# EasyEDA.net
KiCad netlist of a schematic drawn in EasyEDA Pro
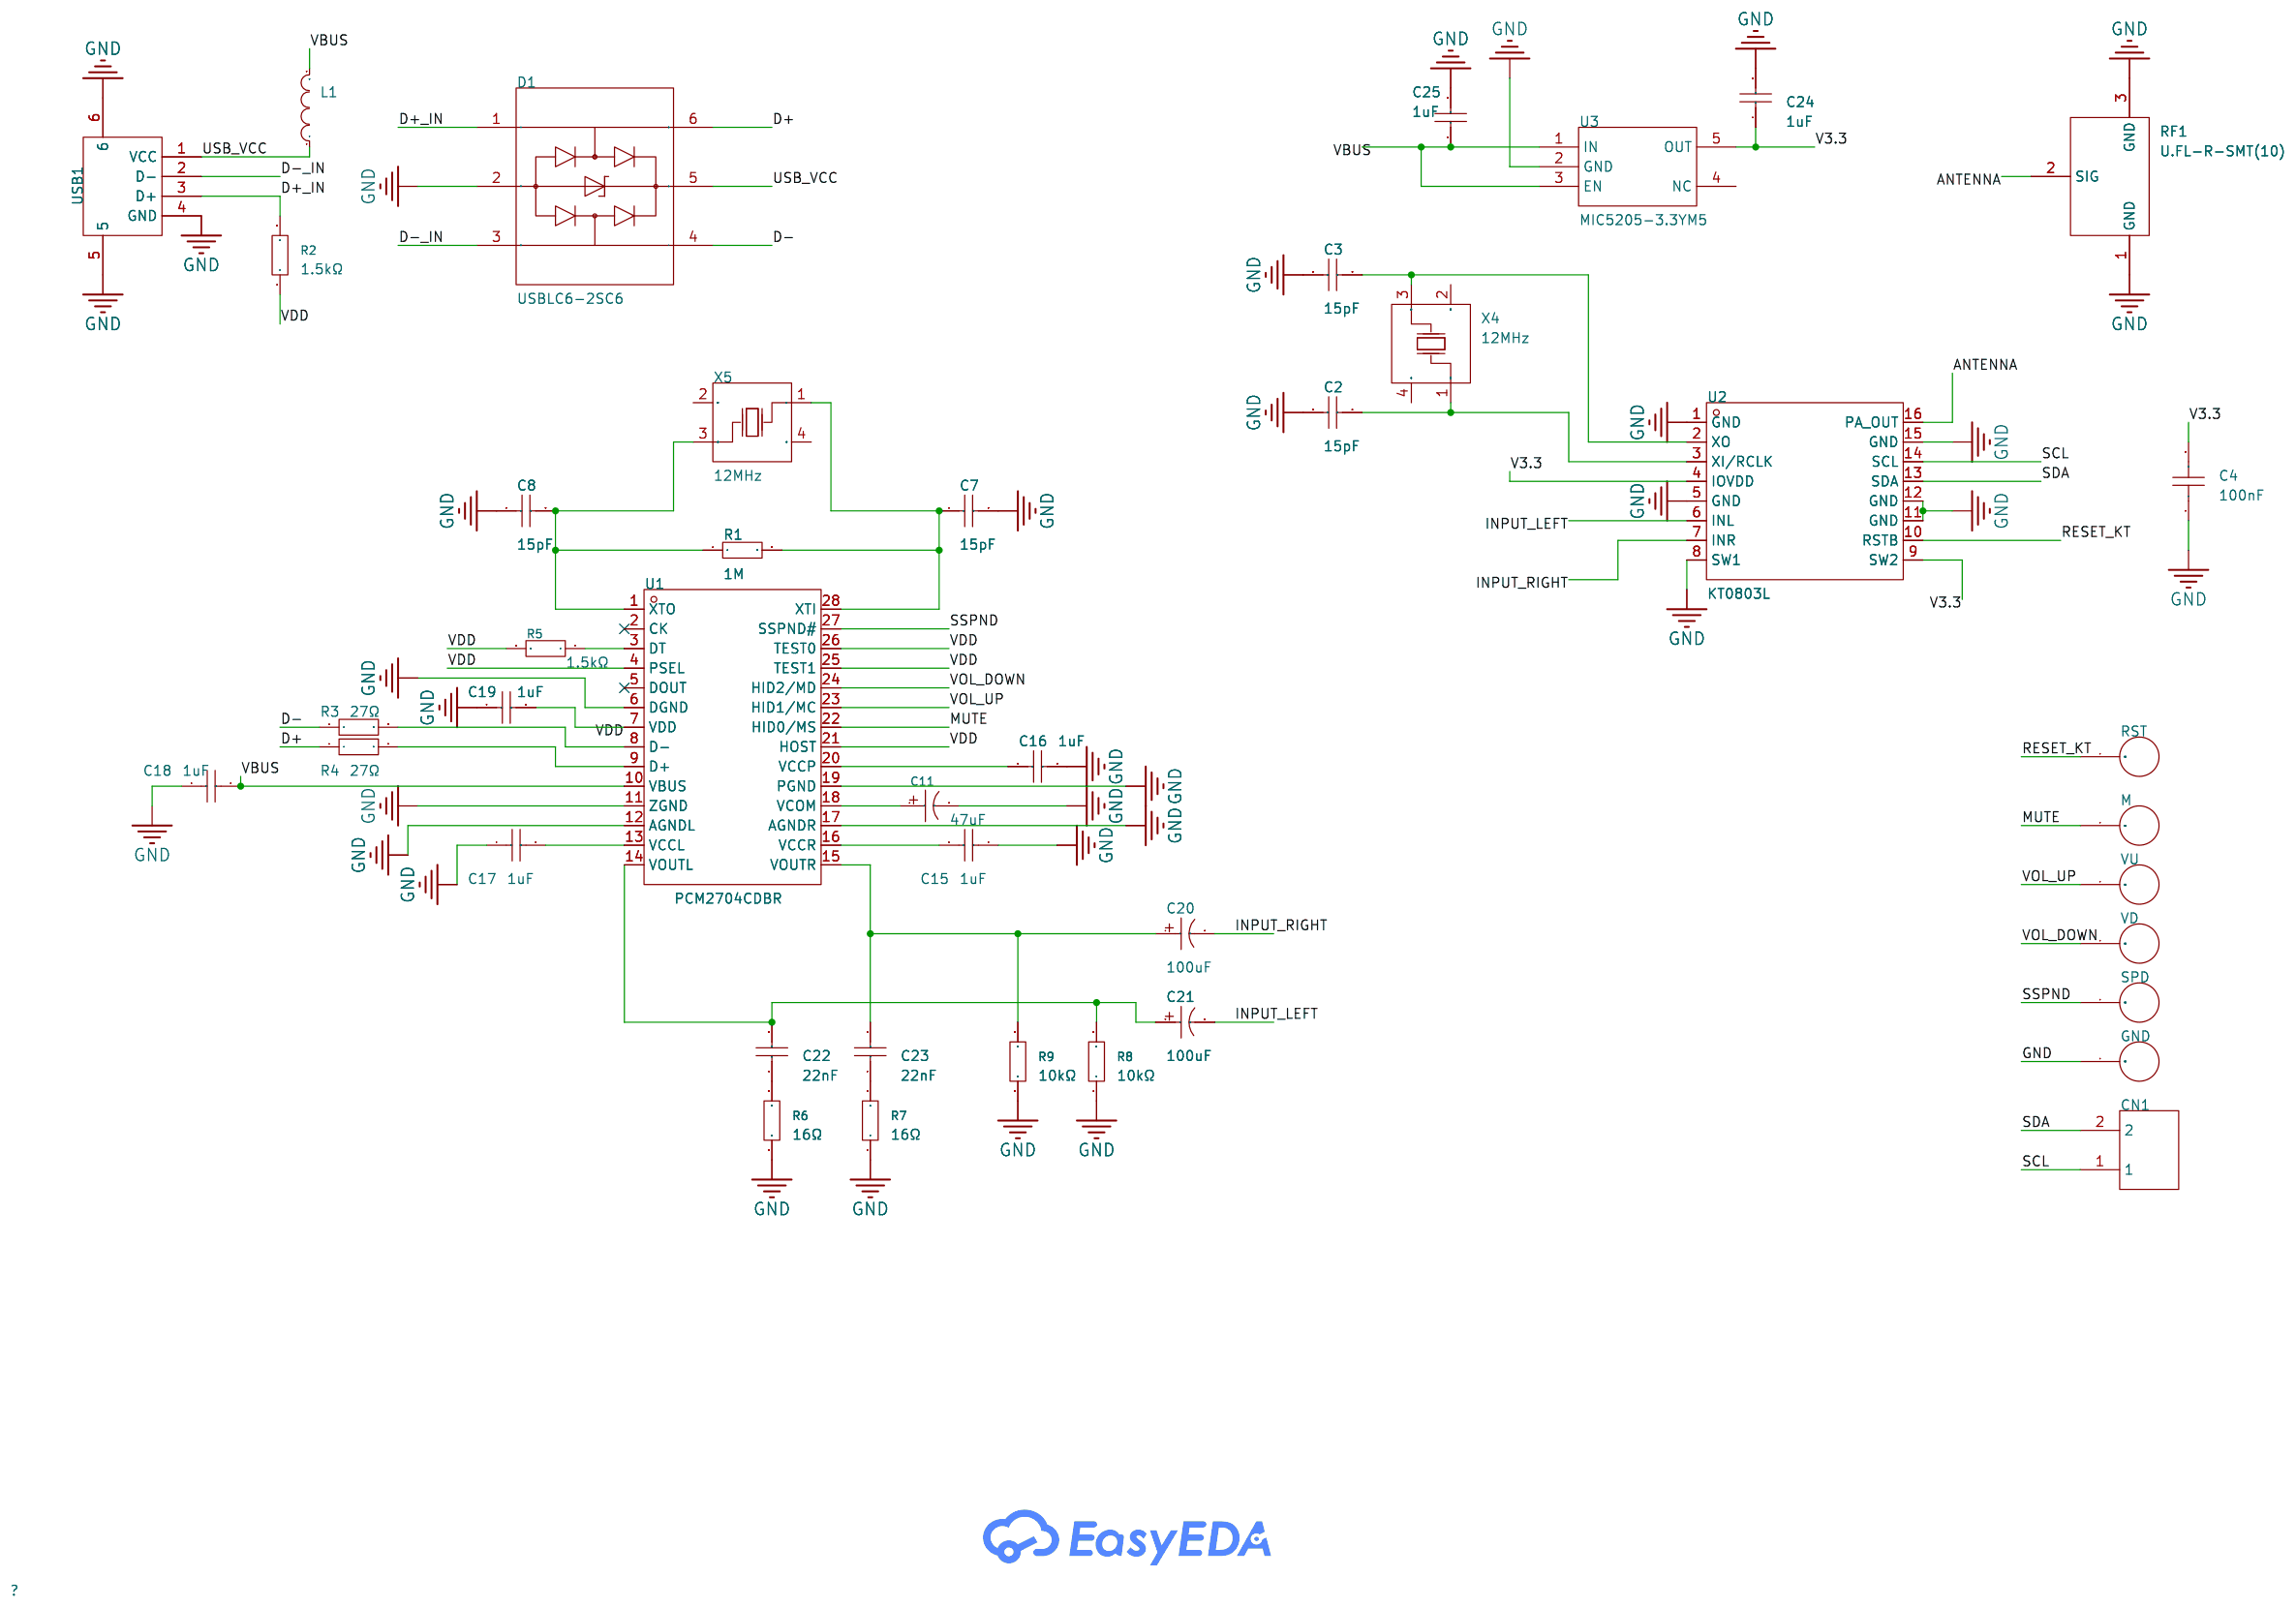
[diagram p0: schematic sheet]

(export (version "E")
  (design (tool "Eeschema 10.0.6"))
  (components
    (comp (ref "C2")
      (value "15pF")
      (footprint "easyedapro:C0402")
      (fields (field (name "Manufacturer Part") "0402CG150J500NT") (field (name "Manufacturer") "FH(风华)"))
      (libsource (lib "easyedapro") (part "0402CG150J500NT"))
    )
    (comp (ref "C3")
      (value "15pF")
      (footprint "easyedapro:C0402")
      (fields (field (name "Manufacturer Part") "0402CG150J500NT") (field (name "Manufacturer") "FH(风华)"))
      (libsource (lib "easyedapro") (part "0402CG150J500NT"))
    )
    (comp (ref "C4")
      (value "100nF")
      (footprint "easyedapro:C0402")
      (fields
        (field (name "Manufacturer Part") "CL05B104KO5NNNC")
        (field (name "Manufacturer") "SAMSUNG(三星)")
      )
      (libsource (lib "easyedapro") (part "CL05B104KO5NNNC"))
    )
    (comp (ref "C7")
      (value "15pF")
      (footprint "easyedapro:C0402")
      (fields (field (name "Manufacturer Part") "0402CG150J500NT") (field (name "Manufacturer") "FH(风华)"))
      (libsource (lib "easyedapro") (part "0402CG150J500NT"))
    )
    (comp (ref "C8")
      (value "15pF")
      (footprint "easyedapro:C0402")
      (fields (field (name "Manufacturer Part") "0402CG150J500NT") (field (name "Manufacturer") "FH(风华)"))
      (libsource (lib "easyedapro") (part "0402CG150J500NT"))
    )
    (comp (ref "C11")
      (value "47uF")
      (footprint "easyedapro:CAP-SMD_BD5.0-L5.3-W5.3-FD")
      (fields (field (name "Manufacturer Part") "RVT1C470M0505") (field (name "Manufacturer") "HONOR(荣誉)"))
      (libsource (lib "easyedapro") (part "RVT1C470M0505"))
    )
    (comp (ref "C15")
      (value "1uF")
      (footprint "easyedapro:C0603")
      (fields
        (field (name "Manufacturer Part") "CL10A105KO8NNNC")
        (field (name "Manufacturer") "SAMSUNG(三星)")
      )
      (libsource (lib "easyedapro") (part "CL10A105KO8NNNC"))
    )
    (comp (ref "C16")
      (value "1uF")
      (footprint "easyedapro:C0603")
      (fields
        (field (name "Manufacturer Part") "CL10A105KO8NNNC")
        (field (name "Manufacturer") "SAMSUNG(三星)")
      )
      (libsource (lib "easyedapro") (part "CL10A105KO8NNNC"))
    )
    (comp (ref "C17")
      (value "1uF")
      (footprint "easyedapro:C0603")
      (fields
        (field (name "Manufacturer Part") "CL10A105KO8NNNC")
        (field (name "Manufacturer") "SAMSUNG(三星)")
      )
      (libsource (lib "easyedapro") (part "CL10A105KO8NNNC"))
    )
    (comp (ref "C18")
      (value "1uF")
      (footprint "easyedapro:C0603")
      (fields
        (field (name "Manufacturer Part") "CL10A105KO8NNNC")
        (field (name "Manufacturer") "SAMSUNG(三星)")
      )
      (libsource (lib "easyedapro") (part "CL10A105KO8NNNC"))
    )
    (comp (ref "C19")
      (value "1uF")
      (footprint "easyedapro:C0603")
      (fields
        (field (name "Manufacturer Part") "CL10A105KO8NNNC")
        (field (name "Manufacturer") "SAMSUNG(三星)")
      )
      (libsource (lib "easyedapro") (part "CL10A105KO8NNNC"))
    )
    (comp (ref "C20")
      (value "100uF")
      (footprint "easyedapro:CAP-SMD_BD6.3-L6.6-W6.6-LS7.2-R-RD")
      (fields (field (name "Manufacturer Part") "RVT1E101M0607") (field (name "Manufacturer") "HONOR(荣誉)"))
      (libsource (lib "easyedapro") (part "RVT1E101M0607"))
    )
    (comp (ref "C21")
      (value "100uF")
      (footprint "easyedapro:CAP-SMD_BD6.3-L6.6-W6.6-LS7.2-R-RD")
      (fields (field (name "Manufacturer Part") "RVT1E101M0607") (field (name "Manufacturer") "HONOR(荣誉)"))
      (libsource (lib "easyedapro") (part "RVT1E101M0607"))
    )
    (comp (ref "C22")
      (value "22nF")
      (footprint "easyedapro:C0402")
      (description "Capacitance:22nF Tolerance:±10% Tolerance:±10% Voltage Rating:50V Temperature Coefficient:X7R")
      (fields (field (name "Manufacturer Part") "0402B223K500NT") (field (name "Manufacturer") "FH(风华)"))
      (libsource (lib "easyedapro") (part "0402B223K500NT"))
    )
    (comp (ref "C23")
      (value "22nF")
      (footprint "easyedapro:C0402")
      (description "Capacitance:22nF Tolerance:±10% Tolerance:±10% Voltage Rating:50V Temperature Coefficient:X7R")
      (fields (field (name "Manufacturer Part") "0402B223K500NT") (field (name "Manufacturer") "FH(风华)"))
      (libsource (lib "easyedapro") (part "0402B223K500NT"))
    )
    (comp (ref "C24")
      (value "1uF")
      (footprint "easyedapro:C0603")
      (fields
        (field (name "Manufacturer Part") "CL10A105KO8NNNC")
        (field (name "Manufacturer") "SAMSUNG(三星)")
      )
      (libsource (lib "easyedapro") (part "CL10A105KO8NNNC"))
    )
    (comp (ref "C25")
      (value "1uF")
      (footprint "easyedapro:C0603")
      (fields
        (field (name "Manufacturer Part") "CL10A105KO8NNNC")
        (field (name "Manufacturer") "SAMSUNG(三星)")
      )
      (libsource (lib "easyedapro") (part "CL10A105KO8NNNC"))
    )
    (comp (ref "CN1")
      (value "B2B-PH-K-S(LF)(SN)")
      (footprint "easyedapro:CONN-TH_B2B-PH-K-S")
      (fields (field (name "Manufacturer") "JST"))
      (libsource (lib "easyedapro") (part "B2B-PH-K-S(LF)(SN)"))
    )
    (comp (ref "D1")
      (value "USBLC6-2SC6")
      (footprint "easyedapro:SOT-23-6_L2.9-W1.6-P0.95-LS2.8-BL")
      (libsource (lib "easyedapro") (part "USBLC6-2SC6_C323793"))
    )
    (comp (ref "GND")
      (value "~")
      (footprint "easyedapro:TEST PAD")
      (libsource (lib "easyedapro") (part "TEST PAD"))
    )
    (comp (ref "L1")
      (value "MPZ1608S101ATAH0")
      (footprint "easyedapro:L0603")
      (fields (field (name "Manufacturer") "TDK"))
      (libsource (lib "easyedapro") (part "MPZ1608S101ATAH0"))
    )
    (comp (ref "M")
      (value "~")
      (footprint "easyedapro:TEST PAD")
      (libsource (lib "easyedapro") (part "TEST PAD"))
    )
    (comp (ref "R1")
      (value "1M")
      (footprint "easyedapro:R0402")
      (fields (field (name "Manufacturer Part") "0402WGF1004TCE") (field (name "Manufacturer") "UniOhm"))
      (libsource (lib "easyedapro") (part "1M"))
    )
    (comp (ref "R2")
      (value "1.5kΩ")
      (footprint "easyedapro:R0402")
      (fields
        (field (name "Manufacturer Part") "0402WGF1501TCE")
        (field (name "Manufacturer") "UNI-ROYAL(厚声)")
      )
      (libsource (lib "easyedapro") (part "0402WGF1501TCE"))
    )
    (comp (ref "R3")
      (value "27Ω")
      (footprint "easyedapro:R0402")
      (fields
        (field (name "Manufacturer Part") "0402WGF270JTCE")
        (field (name "Manufacturer") "UNI-ROYAL(厚声)")
      )
      (libsource (lib "easyedapro") (part "0402WGF270JTCE"))
    )
    (comp (ref "R4")
      (value "27Ω")
      (footprint "easyedapro:R0402")
      (fields
        (field (name "Manufacturer Part") "0402WGF270JTCE")
        (field (name "Manufacturer") "UNI-ROYAL(厚声)")
      )
      (libsource (lib "easyedapro") (part "0402WGF270JTCE"))
    )
    (comp (ref "R5")
      (value "1.5kΩ")
      (footprint "easyedapro:R0402")
      (fields
        (field (name "Manufacturer Part") "0402WGF1501TCE")
        (field (name "Manufacturer") "UNI-ROYAL(厚声)")
      )
      (libsource (lib "easyedapro") (part "0402WGF1501TCE"))
    )
    (comp (ref "R6")
      (value "16Ω")
      (footprint "easyedapro:R0603")
      (fields
        (field (name "Manufacturer Part") "0603WAF160JT5E")
        (field (name "Manufacturer") "UNI-ROYAL(厚声)")
      )
      (libsource (lib "easyedapro") (part "0603WAF160JT5E"))
    )
    (comp (ref "R7")
      (value "16Ω")
      (footprint "easyedapro:R0603")
      (fields
        (field (name "Manufacturer Part") "0603WAF160JT5E")
        (field (name "Manufacturer") "UNI-ROYAL(厚声)")
      )
      (libsource (lib "easyedapro") (part "0603WAF160JT5E"))
    )
    (comp (ref "R8")
      (value "10kΩ")
      (footprint "easyedapro:R0402")
      (fields
        (field (name "Manufacturer Part") "0402WGJ0103TCE")
        (field (name "Manufacturer") "UNI-ROYAL(厚声)")
      )
      (libsource (lib "easyedapro") (part "0402WGJ0103TCE"))
    )
    (comp (ref "R9")
      (value "10kΩ")
      (footprint "easyedapro:R0402")
      (fields
        (field (name "Manufacturer Part") "0402WGJ0103TCE")
        (field (name "Manufacturer") "UNI-ROYAL(厚声)")
      )
      (libsource (lib "easyedapro") (part "0402WGJ0103TCE"))
    )
    (comp (ref "RF1")
      (value "U.FL-R-SMT(10)")
      (footprint "easyedapro:ANT-SMD_UFL-R-SMT01")
      (fields (field (name "Manufacturer") "HRS(广濑)"))
      (libsource (lib "easyedapro") (part "U.FL-R-SMT(10)"))
    )
    (comp (ref "RST")
      (value "~")
      (footprint "easyedapro:TEST PAD")
      (libsource (lib "easyedapro") (part "TEST PAD"))
    )
    (comp (ref "SPD")
      (value "~")
      (footprint "easyedapro:TEST PAD")
      (libsource (lib "easyedapro") (part "TEST PAD"))
    )
    (comp (ref "U1")
      (value "PCM2704CDBR")
      (footprint "easyedapro:SSOP-28_L10.2-W5.3-P0.65-LS7.8-BL")
      (fields (field (name "Manufacturer") "TI(德州仪器)"))
      (libsource (lib "easyedapro") (part "PCM2704CDBR"))
    )
    (comp (ref "U2")
      (value "KT0803L")
      (footprint "easyedapro:SOP-16_L9.9-W3.9-P1.27-LS6.0-BL")
      (libsource (lib "easyedapro") (part "KT0803L"))
    )
    (comp (ref "U3")
      (value "MIC5205-3.3YM5")
      (footprint "easyedapro:SOT-23-5_L3.0-W1.7-P0.95-LS2.8-BR")
      (fields (field (name "Manufacturer") "TECH PUBLIC(台舟)"))
      (libsource (lib "easyedapro") (part "TLV73333PDBVR"))
    )
    (comp (ref "USB1")
      (value "U-G-O4DD-W-1")
      (footprint "easyedapro:USB-A-TH_U-G-04WD-W-01")
      (fields (field (name "Manufacturer") "韩国韩荣"))
      (libsource (lib "easyedapro") (part "U-G-04DD-W-01"))
    )
    (comp (ref "VD")
      (value "~")
      (footprint "easyedapro:TEST PAD")
      (libsource (lib "easyedapro") (part "TEST PAD"))
    )
    (comp (ref "VU")
      (value "~")
      (footprint "easyedapro:TEST PAD")
      (libsource (lib "easyedapro") (part "TEST PAD"))
    )
    (comp (ref "X4")
      (value "12MHz")
      (footprint "easyedapro:CRYSTAL-SMD_4P-L3.2-W2.5-BL")
      (fields (field (name "Manufacturer Part") "X322512MSB4SI") (field (name "Manufacturer") "YXC(扬兴晶振)"))
      (libsource (lib "easyedapro") (part "X322512MSB4SI"))
    )
    (comp (ref "X5")
      (value "12MHz")
      (footprint "easyedapro:CRYSTAL-SMD_4P-L3.2-W2.5-BL")
      (fields (field (name "Manufacturer Part") "X322512MSB4SI") (field (name "Manufacturer") "YXC(扬兴晶振)"))
      (libsource (lib "easyedapro") (part "X322512MSB4SI"))
    )
  )
  (nets
    (net (code "1") (name "/ANTENNA") (class "Default")
      (node (ref "RF1") (pin "2") (pinfunction "SIG_2") (pintype "unspecified"))
      (node (ref "U2") (pin "16") (pinfunction "PA_OUT_16") (pintype "unspecified"))
    )
    (net (code "2") (name "/D+") (class "Default")
      (node (ref "D1") (pin "6") (pinfunction "6_6") (pintype "input"))
      (node (ref "R4") (pin "1") (pinfunction "1_1") (pintype "input"))
    )
    (net (code "3") (name "/D+_IN") (class "Default")
      (node (ref "D1") (pin "1") (pinfunction "1_1") (pintype "input"))
      (node (ref "R2") (pin "2") (pinfunction "2_2") (pintype "input"))
      (node (ref "USB1") (pin "3") (pinfunction "D+_3") (pintype "unspecified"))
    )
    (net (code "4") (name "/D-") (class "Default")
      (node (ref "D1") (pin "4") (pinfunction "4_4") (pintype "input"))
      (node (ref "R3") (pin "1") (pinfunction "1_1") (pintype "input"))
    )
    (net (code "5") (name "/D-_IN") (class "Default")
      (node (ref "D1") (pin "3") (pinfunction "3_3") (pintype "input"))
      (node (ref "USB1") (pin "2") (pinfunction "D-_2") (pintype "unspecified"))
    )
    (net (code "6") (name "/INPUT_LEFT") (class "Default")
      (node (ref "C21") (pin "2") (pinfunction "2_2") (pintype "input"))
      (node (ref "U2") (pin "6") (pinfunction "INL_6") (pintype "unspecified"))
    )
    (net (code "7") (name "/INPUT_RIGHT") (class "Default")
      (node (ref "C20") (pin "2") (pinfunction "2_2") (pintype "input"))
      (node (ref "U2") (pin "7") (pinfunction "INR_7") (pintype "unspecified"))
    )
    (net (code "8") (name "/MUTE") (class "Default")
      (node (ref "M") (pin "1") (pinfunction "TEST_PAD1_1") (pintype "input"))
      (node (ref "U1") (pin "22") (pinfunction "HID0/MS_22") (pintype "unspecified"))
    )
    (net (code "9") (name "/RESET_KT") (class "Default")
      (node (ref "RST") (pin "1") (pinfunction "TEST_PAD1_1") (pintype "input"))
      (node (ref "U2") (pin "10") (pinfunction "RSTB_10") (pintype "unspecified"))
    )
    (net (code "10") (name "/SCL") (class "Default")
      (node (ref "CN1") (pin "1") (pinfunction "1_1") (pintype "input"))
      (node (ref "U2") (pin "14") (pinfunction "SCL_14") (pintype "unspecified"))
    )
    (net (code "11") (name "/SDA") (class "Default")
      (node (ref "CN1") (pin "2") (pinfunction "2_2") (pintype "input"))
      (node (ref "U2") (pin "13") (pinfunction "SDA_13") (pintype "unspecified"))
    )
    (net (code "12") (name "/SSPND") (class "Default")
      (node (ref "SPD") (pin "1") (pinfunction "TEST_PAD1_1") (pintype "input"))
      (node (ref "U1") (pin "27") (pinfunction "SSPND#_27") (pintype "unspecified"))
    )
    (net (code "13") (name "/USB_VCC") (class "Default")
      (node (ref "D1") (pin "5") (pinfunction "5_5") (pintype "input"))
      (node (ref "L1") (pin "1") (pinfunction "1_1") (pintype "unspecified"))
      (node (ref "USB1") (pin "1") (pinfunction "VCC_1") (pintype "unspecified"))
    )
    (net (code "14") (name "/V3.3") (class "Default")
      (node (ref "C24") (pin "1") (pinfunction "1_1") (pintype "input"))
      (node (ref "C4") (pin "2") (pinfunction "2_2") (pintype "unspecified"))
      (node (ref "U2") (pin "4") (pinfunction "IOVDD_4") (pintype "unspecified"))
      (node (ref "U2") (pin "9") (pinfunction "SW2_9") (pintype "unspecified"))
      (node (ref "U3") (pin "5") (pinfunction "OUT_5") (pintype "unspecified"))
    )
    (net (code "15") (name "/VBUS") (class "Default")
      (node (ref "C18") (pin "2") (pinfunction "2_2") (pintype "input"))
      (node (ref "C25") (pin "1") (pinfunction "1_1") (pintype "input"))
      (node (ref "L1") (pin "2") (pinfunction "2_2") (pintype "unspecified"))
      (node (ref "U1") (pin "10") (pinfunction "VBUS_10") (pintype "unspecified"))
      (node (ref "U3") (pin "1") (pinfunction "IN_1") (pintype "unspecified"))
      (node (ref "U3") (pin "3") (pinfunction "EN_3") (pintype "unspecified"))
    )
    (net (code "16") (name "/VDD") (class "Default")
      (node (ref "C19") (pin "2") (pinfunction "2_2") (pintype "input"))
      (node (ref "R2") (pin "1") (pinfunction "1_1") (pintype "input"))
      (node (ref "R5") (pin "2") (pinfunction "2_2") (pintype "input"))
      (node (ref "U1") (pin "21") (pinfunction "HOST_21") (pintype "unspecified"))
      (node (ref "U1") (pin "25") (pinfunction "TEST1_25") (pintype "unspecified"))
      (node (ref "U1") (pin "26") (pinfunction "TEST0_26") (pintype "unspecified"))
      (node (ref "U1") (pin "4") (pinfunction "PSEL_4") (pintype "unspecified"))
      (node (ref "U1") (pin "7") (pinfunction "VDD_7") (pintype "unspecified"))
    )
    (net (code "17") (name "/VOL_DOWN") (class "Default")
      (node (ref "U1") (pin "24") (pinfunction "HID2/MD_24") (pintype "unspecified"))
      (node (ref "VD") (pin "1") (pinfunction "TEST_PAD1_1") (pintype "input"))
    )
    (net (code "18") (name "/VOL_UP") (class "Default")
      (node (ref "U1") (pin "23") (pinfunction "HID1/MC_23") (pintype "unspecified"))
      (node (ref "VU") (pin "1") (pinfunction "TEST_PAD1_1") (pintype "input"))
    )
    (net (code "19") (name "GND") (class "Default")
      (node (ref "C11") (pin "2") (pinfunction "2_2") (pintype "input"))
      (node (ref "C15") (pin "2") (pinfunction "2_2") (pintype "input"))
      (node (ref "C16") (pin "2") (pinfunction "2_2") (pintype "input"))
      (node (ref "C17") (pin "1") (pinfunction "1_1") (pintype "input"))
      (node (ref "C18") (pin "1") (pinfunction "1_1") (pintype "input"))
      (node (ref "C19") (pin "1") (pinfunction "1_1") (pintype "input"))
      (node (ref "C2") (pin "1") (pinfunction "1_1") (pintype "input"))
      (node (ref "C24") (pin "2") (pinfunction "2_2") (pintype "input"))
      (node (ref "C25") (pin "2") (pinfunction "2_2") (pintype "input"))
      (node (ref "C3") (pin "1") (pinfunction "1_1") (pintype "input"))
      (node (ref "C4") (pin "1") (pinfunction "1_1") (pintype "unspecified"))
      (node (ref "C7") (pin "2") (pinfunction "2_2") (pintype "input"))
      (node (ref "C8") (pin "1") (pinfunction "1_1") (pintype "input"))
      (node (ref "D1") (pin "2") (pinfunction "2_2") (pintype "input"))
      (node (ref "GND") (pin "1") (pinfunction "TEST_PAD1_1") (pintype "input"))
      (node (ref "R6") (pin "1") (pinfunction "1_1") (pintype "input"))
      (node (ref "R7") (pin "1") (pinfunction "1_1") (pintype "input"))
      (node (ref "R8") (pin "1") (pinfunction "1_1") (pintype "input"))
      (node (ref "R9") (pin "1") (pinfunction "1_1") (pintype "input"))
      (node (ref "RF1") (pin "1") (pinfunction "GND_1") (pintype "unspecified"))
      (node (ref "RF1") (pin "3") (pinfunction "GND_3") (pintype "unspecified"))
      (node (ref "U1") (pin "11") (pinfunction "ZGND_11") (pintype "unspecified"))
      (node (ref "U1") (pin "12") (pinfunction "AGNDL_12") (pintype "unspecified"))
      (node (ref "U1") (pin "17") (pinfunction "AGNDR_17") (pintype "unspecified"))
      (node (ref "U1") (pin "19") (pinfunction "PGND_19") (pintype "unspecified"))
      (node (ref "U1") (pin "6") (pinfunction "DGND_6") (pintype "unspecified"))
      (node (ref "U2") (pin "1") (pinfunction "GND_1") (pintype "unspecified"))
      (node (ref "U2") (pin "11") (pinfunction "GND_11") (pintype "unspecified"))
      (node (ref "U2") (pin "12") (pinfunction "GND_12") (pintype "unspecified"))
      (node (ref "U2") (pin "15") (pinfunction "GND_15") (pintype "unspecified"))
      (node (ref "U2") (pin "5") (pinfunction "GND_5") (pintype "unspecified"))
      (node (ref "U2") (pin "8") (pinfunction "SW1_8") (pintype "unspecified"))
      (node (ref "U3") (pin "2") (pinfunction "GND_2") (pintype "unspecified"))
      (node (ref "USB1") (pin "4") (pinfunction "GND_4") (pintype "unspecified"))
      (node (ref "USB1") (pin "5") (pinfunction "5_5") (pintype "unspecified"))
      (node (ref "USB1") (pin "6") (pinfunction "6_6") (pintype "unspecified"))
    )
    (net (code "20") (name "Net-(C22-Pad1)") (class "Default")
      (node (ref "C22") (pin "1") (pinfunction "1_1") (pintype "input"))
      (node (ref "R6") (pin "2") (pinfunction "2_2") (pintype "input"))
    )
    (net (code "21") (name "Net-(C23-Pad1)") (class "Default")
      (node (ref "C23") (pin "1") (pinfunction "1_1") (pintype "input"))
      (node (ref "R7") (pin "2") (pinfunction "2_2") (pintype "input"))
    )
    (net (code "22") (name "Net-(U1-D+)") (class "Default")
      (node (ref "R4") (pin "2") (pinfunction "2_2") (pintype "input"))
      (node (ref "U1") (pin "9") (pinfunction "D+_9") (pintype "unspecified"))
    )
    (net (code "23") (name "Net-(U1-D-)") (class "Default")
      (node (ref "R3") (pin "2") (pinfunction "2_2") (pintype "input"))
      (node (ref "U1") (pin "8") (pinfunction "D-_8") (pintype "unspecified"))
    )
    (net (code "24") (name "Net-(U1-DT)") (class "Default")
      (node (ref "R5") (pin "1") (pinfunction "1_1") (pintype "input"))
      (node (ref "U1") (pin "3") (pinfunction "DT_3") (pintype "unspecified"))
    )
    (net (code "25") (name "Net-(U1-VCCL)") (class "Default")
      (node (ref "C17") (pin "2") (pinfunction "2_2") (pintype "input"))
      (node (ref "U1") (pin "13") (pinfunction "VCCL_13") (pintype "unspecified"))
    )
    (net (code "26") (name "Net-(U1-VCCP)") (class "Default")
      (node (ref "C16") (pin "1") (pinfunction "1_1") (pintype "input"))
      (node (ref "U1") (pin "20") (pinfunction "VCCP_20") (pintype "unspecified"))
    )
    (net (code "27") (name "Net-(U1-VCCR)") (class "Default")
      (node (ref "C15") (pin "1") (pinfunction "1_1") (pintype "input"))
      (node (ref "U1") (pin "16") (pinfunction "VCCR_16") (pintype "unspecified"))
    )
    (net (code "28") (name "Net-(U1-VCOM)") (class "Default")
      (node (ref "C11") (pin "1") (pinfunction "1_1") (pintype "input"))
      (node (ref "U1") (pin "18") (pinfunction "VCOM_18") (pintype "unspecified"))
    )
    (net (code "29") (name "Net-(U1-VOUTL)") (class "Default")
      (node (ref "C21") (pin "1") (pinfunction "1_1") (pintype "input"))
      (node (ref "C22") (pin "2") (pinfunction "2_2") (pintype "input"))
      (node (ref "R8") (pin "2") (pinfunction "2_2") (pintype "input"))
      (node (ref "U1") (pin "14") (pinfunction "VOUTL_14") (pintype "unspecified"))
    )
    (net (code "30") (name "Net-(U1-VOUTR)") (class "Default")
      (node (ref "C20") (pin "1") (pinfunction "1_1") (pintype "input"))
      (node (ref "C23") (pin "2") (pinfunction "2_2") (pintype "input"))
      (node (ref "R9") (pin "2") (pinfunction "2_2") (pintype "input"))
      (node (ref "U1") (pin "15") (pinfunction "VOUTR_15") (pintype "unspecified"))
    )
    (net (code "31") (name "Net-(U1-XTI)") (class "Default")
      (node (ref "C7") (pin "1") (pinfunction "1_1") (pintype "input"))
      (node (ref "R1") (pin "2") (pinfunction "2_2") (pintype "input"))
      (node (ref "U1") (pin "28") (pinfunction "XTI_28") (pintype "unspecified"))
      (node (ref "X5") (pin "1") (pinfunction "OSC1_1") (pintype "unspecified"))
    )
    (net (code "32") (name "Net-(U1-XTO)") (class "Default")
      (node (ref "C8") (pin "2") (pinfunction "2_2") (pintype "input"))
      (node (ref "R1") (pin "1") (pinfunction "1_1") (pintype "input"))
      (node (ref "U1") (pin "1") (pinfunction "XTO_1") (pintype "unspecified"))
      (node (ref "X5") (pin "3") (pinfunction "OSC2_3") (pintype "unspecified"))
    )
    (net (code "33") (name "Net-(U2-XI{slash}RCLK)") (class "Default")
      (node (ref "C2") (pin "2") (pinfunction "2_2") (pintype "input"))
      (node (ref "U2") (pin "3") (pinfunction "XI/RCLK_3") (pintype "unspecified"))
      (node (ref "X4") (pin "1") (pinfunction "OSC1_1") (pintype "unspecified"))
    )
    (net (code "34") (name "Net-(U2-XO)") (class "Default")
      (node (ref "C3") (pin "2") (pinfunction "2_2") (pintype "input"))
      (node (ref "U2") (pin "2") (pinfunction "XO_2") (pintype "unspecified"))
      (node (ref "X4") (pin "3") (pinfunction "OSC2_3") (pintype "unspecified"))
    )
    (net (code "35") (name "unconnected-(U1-CK-Pad2)") (class "Default")
      (node (ref "U1") (pin "2") (pinfunction "CK_2") (pintype "unspecified+no_connect"))
    )
    (net (code "36") (name "unconnected-(U1-DOUT-Pad5)") (class "Default")
      (node (ref "U1") (pin "5") (pinfunction "DOUT_5") (pintype "unspecified+no_connect"))
    )
    (net (code "37") (name "unconnected-(U3-NC-Pad4)") (class "Default")
      (node (ref "U3") (pin "4") (pinfunction "NC_4") (pintype "unspecified"))
    )
    (net (code "38") (name "unconnected-(X4-GND-Pad2)") (class "Default")
      (node (ref "X4") (pin "2") (pinfunction "GND_2") (pintype "unspecified"))
    )
    (net (code "39") (name "unconnected-(X4-GND-Pad4)") (class "Default")
      (node (ref "X4") (pin "4") (pinfunction "GND_4") (pintype "unspecified"))
    )
    (net (code "40") (name "unconnected-(X5-GND-Pad2)") (class "Default")
      (node (ref "X5") (pin "2") (pinfunction "GND_2") (pintype "unspecified"))
    )
    (net (code "41") (name "unconnected-(X5-GND-Pad4)") (class "Default")
      (node (ref "X5") (pin "4") (pinfunction "GND_4") (pintype "unspecified"))
    )
  )
)
